# ST_LINK_V2-1.net
KiCad netlist of a schematic drawn in Altium Designer
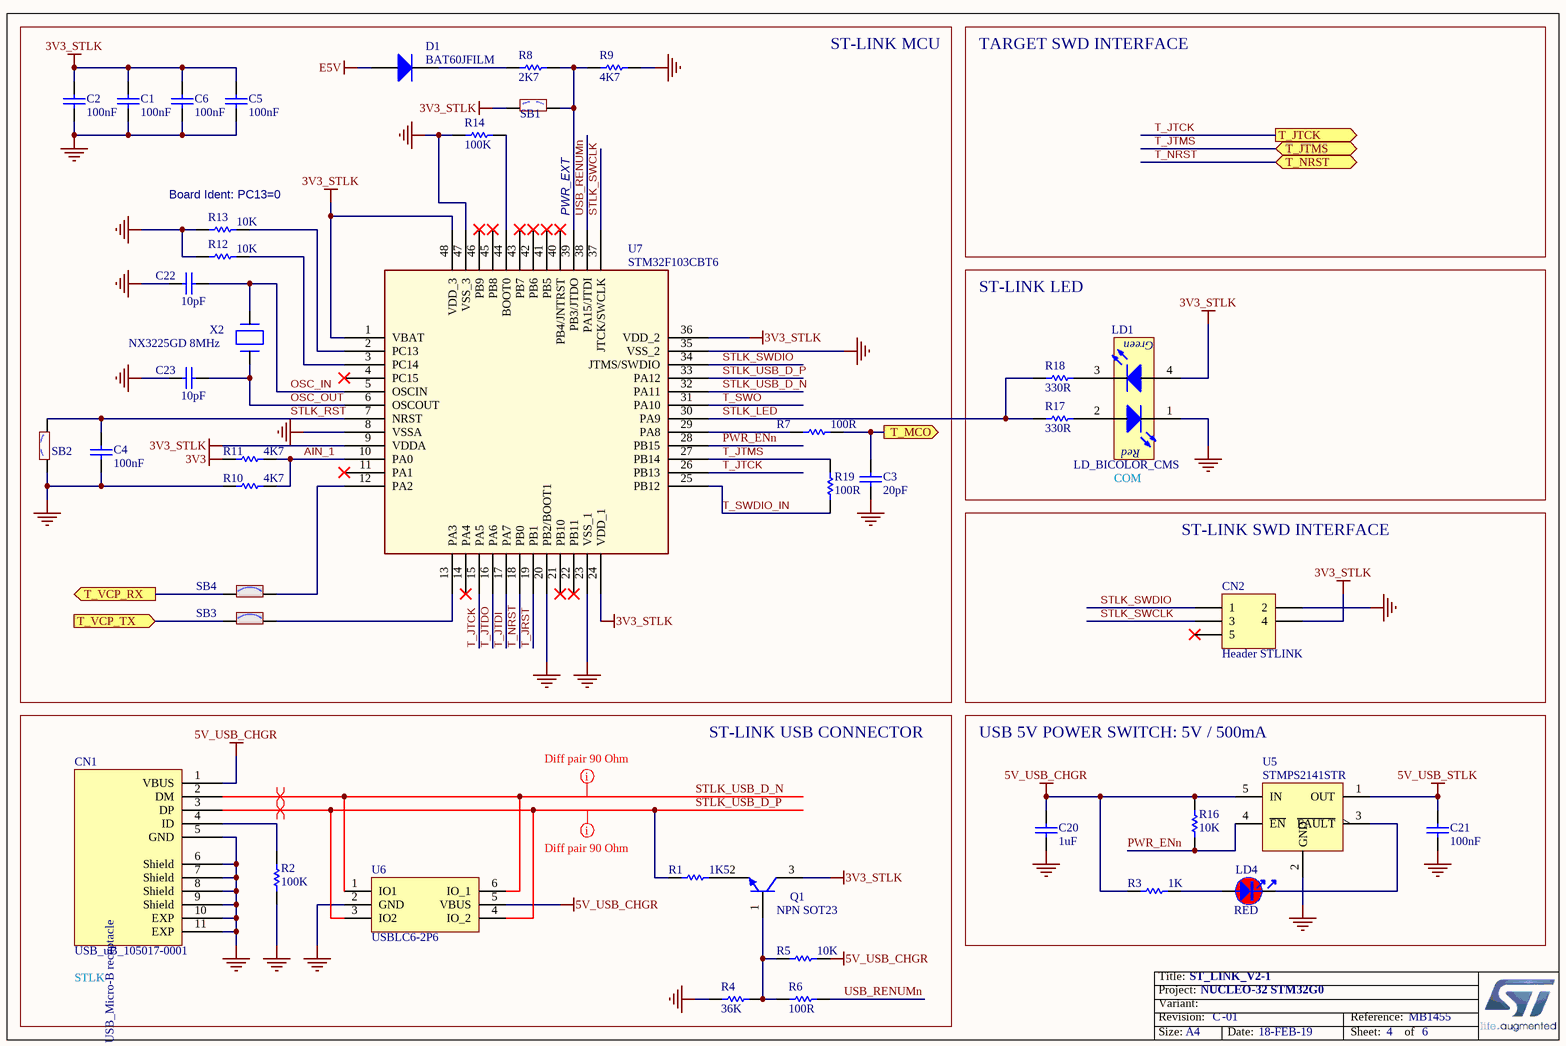
[diagram p0: ST_LINK_V2-1.SCHDOC]

(export (version "E")
  (design (tool "Eeschema 10.0.6"))
  (components
    (comp (ref "C1")
      (value "100nF")
      (footprint "C0402")
      (description "Capacitor, MLCC, 100nF, 16V, X7R, 10%, 0402, T=0,5mm")
      (fields
        (field (name "INTERNAL_PART_NUMBER") "MCD-00102")
        (field (name "MANUFACTURER_PART_NUMBER") "CC0402KRX7R7BB104")
        (field (name "PROVIDED_BY") "SUBCO")
      )
      (libsource (lib "MCD_PARTS_database") (part "Capacitor"))
    )
    (comp (ref "C2")
      (value "100nF")
      (footprint "C0402")
      (description "Capacitor, MLCC, 100nF, 16V, X7R, 10%, 0402, T=0,5mm")
      (fields
        (field (name "INTERNAL_PART_NUMBER") "MCD-00102")
        (field (name "MANUFACTURER_PART_NUMBER") "CC0402KRX7R7BB104")
        (field (name "PROVIDED_BY") "SUBCO")
      )
      (libsource (lib "MCD_PARTS_database") (part "Capacitor"))
    )
    (comp (ref "C3")
      (value "20pF")
      (footprint "C0402")
      (description "Capacitor, MLCC, 20pF, 50V, NPO, 5%, 0402, T=0,5mm")
      (fields
        (field (name "INTERNAL_PART_NUMBER") "MCD-00016")
        (field (name "MANUFACTURER_PART_NUMBER") "CC0402JRNPO9BN200")
        (field (name "PROVIDED_BY") "SUBCO")
      )
      (libsource (lib "MCD_PARTS_database") (part "Capacitor"))
    )
    (comp (ref "C4")
      (value "100nF")
      (footprint "C0402")
      (description "Capacitor, MLCC, 100nF, 16V, X7R, 10%, 0402, T=0,5mm")
      (fields
        (field (name "INTERNAL_PART_NUMBER") "MCD-00102")
        (field (name "MANUFACTURER_PART_NUMBER") "CC0402KRX7R7BB104")
        (field (name "PROVIDED_BY") "SUBCO")
      )
      (libsource (lib "MCD_PARTS_database") (part "Capacitor"))
    )
    (comp (ref "C5")
      (value "100nF")
      (footprint "C0402")
      (description "Capacitor, MLCC, 100nF, 16V, X7R, 10%, 0402, T=0,5mm")
      (fields
        (field (name "INTERNAL_PART_NUMBER") "MCD-00102")
        (field (name "MANUFACTURER_PART_NUMBER") "CC0402KRX7R7BB104")
        (field (name "PROVIDED_BY") "SUBCO")
      )
      (libsource (lib "MCD_PARTS_database") (part "Capacitor"))
    )
    (comp (ref "C6")
      (value "100nF")
      (footprint "C0402")
      (description "Capacitor, MLCC, 100nF, 16V, X7R, 10%, 0402, T=0,5mm")
      (fields
        (field (name "INTERNAL_PART_NUMBER") "MCD-00102")
        (field (name "MANUFACTURER_PART_NUMBER") "CC0402KRX7R7BB104")
        (field (name "PROVIDED_BY") "SUBCO")
      )
      (libsource (lib "MCD_PARTS_database") (part "Capacitor"))
    )
    (comp (ref "C20")
      (value "1uF")
      (footprint "C0402")
      (description "Capacitor, MLCC, 1uF, 6V3, X5R, 10%, 0402, T=0,5mm")
      (fields
        (field (name "INTERNAL_PART_NUMBER") "MCD-00095")
        (field (name "MANUFACTURER_PART_NUMBER") "GRM155R61E105KA12")
        (field (name "PROVIDED_BY") "SUBCO")
      )
      (libsource (lib "MCD_PARTS_database") (part "Capacitor"))
    )
    (comp (ref "C21")
      (value "100nF")
      (footprint "C0402")
      (description "Capacitor, MLCC, 100nF, 16V, X7R, 10%, 0402, T=0,5mm")
      (fields
        (field (name "INTERNAL_PART_NUMBER") "MCD-00102")
        (field (name "MANUFACTURER_PART_NUMBER") "CC0402KRX7R7BB104")
        (field (name "PROVIDED_BY") "SUBCO")
      )
      (libsource (lib "MCD_PARTS_database") (part "Capacitor"))
    )
    (comp (ref "C22")
      (value "10pF")
      (footprint "C0402")
      (description "Capacitor, MLCC, 10pF, 50V, NPO, 5%, 0402, T=0,5mm")
      (fields
        (field (name "INTERNAL_PART_NUMBER") "MCD-00015")
        (field (name "MANUFACTURER_PART_NUMBER") "CC0402JRNPO9BN100")
        (field (name "PROVIDED_BY") "SUBCO")
      )
      (libsource (lib "MCD_PARTS_database") (part "Capacitor"))
    )
    (comp (ref "C23")
      (value "10pF")
      (footprint "C0402")
      (description "Capacitor, MLCC, 10pF, 50V, NPO, 5%, 0402, T=0,5mm")
      (fields
        (field (name "INTERNAL_PART_NUMBER") "MCD-00015")
        (field (name "MANUFACTURER_PART_NUMBER") "CC0402JRNPO9BN100")
        (field (name "PROVIDED_BY") "SUBCO")
      )
      (libsource (lib "MCD_PARTS_database") (part "Capacitor"))
    )
    (comp (ref "CN1")
      (value "USB_uB_105017-0001")
      (footprint "CON_USBMICROB_MOLEX_105017-0001_H2P90")
      (description "USB-MICRO-B, 0.65mm, RA, SMT, Bottom Mount,")
      (fields
        (field (name "INTERNAL_PART_NUMBER") "MCD-00028")
        (field (name "MANUFACTURER_PART_NUMBER") "1050170001")
        (field (name "PROVIDED_BY") "SUBCO")
      )
      (libsource (lib "MCD_PARTS_database") (part "USB_uB_105017.0001"))
    )
    (comp (ref "CN2")
      (value "Header STLINK")
      (footprint "HDR_1x5_2R54_V_M")
      (description "Header 5 pads for ST-LINK prog. Not fitted")
      (fields
        (field (name "INTERNAL_PART_NUMBER") "MCD-01399")
        (field (name "MANUFACTURER_PART_NUMBER") "n/a")
        (field (name "PROVIDED_BY") "SUBCO")
      )
      (libsource (lib "MCD_PARTS_database") (part "Header STLINK"))
    )
    (comp (ref "D1")
      (value "BAT60JFILM")
      (footprint "DIO_SOD323")
      (fields
        (field (name "INTERNAL_PART_NUMBER") "MCD-00034")
        (field (name "MANUFACTURER") "STMICROELECTRONICS")
        (field (name "BMS_PART_NUMBER") "9151097")
        (field (name "PROVIDED_BY") "SUBCO with ST control")
      )
      (libsource (lib "MCD_PARTS_database") (part "BAT60JFILM"))
    )
    (comp (ref "LD1")
      (value "LD_BICOLOR_CMS")
      (footprint "LED_BI-GR_HSMF-A201-A00J1")
      (description "LED Bicolor")
      (fields
        (field (name "INTERNAL_PART_NUMBER") "MCD-00051")
        (field (name "MANUFACTURER_PART_NUMBER") "HSMF-A201-A00J1")
        (field (name "PROVIDED_BY") "SUBCO")
      )
      (libsource (lib "MCD_PARTS_database") (part "LD_BICOLOR_CMS"))
    )
    (comp (ref "LD4")
      (value "RED")
      (footprint "LED_0603_RED_H0P4")
      (description "LED, Red, 0603")
      (fields
        (field (name "INTERNAL_PART_NUMBER") "MCD-00322")
        (field (name "MANUFACTURER_PART_NUMBER") "19-217/R6C-AL1M2VY/3T")
        (field (name "PROVIDED_BY") "SUBCO")
      )
      (libsource (lib "MCD_PARTS_database") (part "LED_red"))
    )
    (comp (ref "Q1")
      (value "NPN SOT23")
      (footprint "NPN_SOT23")
      (description "NPN Bipolar Transistor")
      (fields
        (field (name "INTERNAL_PART_NUMBER") "MCD-00073")
        (field (name "MANUFACTURER_PART_NUMBER") "BSR14")
        (field (name "PROVIDED_BY") "SUBCO")
      )
      (libsource (lib "MCD_PARTS_database") (part "9013-SOT23"))
    )
    (comp (ref "R1")
      (value "1K5")
      (footprint "R0402")
      (description "Resistor,1K5,0402,1%,1/16W")
      (fields
        (field (name "INTERNAL_PART_NUMBER") "MCD-00068")
        (field (name "MANUFACTURER_PART_NUMBER") "RC0402FR-071K5L")
        (field (name "PROVIDED_BY") "SUBCO")
      )
      (libsource (lib "MCD_PARTS_database") (part "Resistor"))
    )
    (comp (ref "R2")
      (value "100K")
      (footprint "R0402")
      (description "Resistor,100K,0402,1%,1/16W")
      (fields
        (field (name "INTERNAL_PART_NUMBER") "MCD-00059")
        (field (name "MANUFACTURER_PART_NUMBER") "RC0402FR-07100KL")
        (field (name "PROVIDED_BY") "SUBCO")
      )
      (libsource (lib "MCD_PARTS_database") (part "Resistor"))
    )
    (comp (ref "R3")
      (value "1K")
      (footprint "R0402")
      (description "Resistor,1K,0402,1%,1/16W")
      (fields
        (field (name "INTERNAL_PART_NUMBER") "MCD-00061")
        (field (name "MANUFACTURER_PART_NUMBER") "RC0402FR-071KL")
        (field (name "PROVIDED_BY") "SUBCO")
      )
      (libsource (lib "MCD_PARTS_database") (part "Resistor"))
    )
    (comp (ref "R4")
      (value "36K")
      (footprint "R0402")
      (description "Resistor,36K,0402,1%,1/16W")
      (fields
        (field (name "INTERNAL_PART_NUMBER") "MCD-00069")
        (field (name "MANUFACTURER_PART_NUMBER") "RC0402FR-0736KL")
        (field (name "PROVIDED_BY") "SUBCO")
      )
      (libsource (lib "MCD_PARTS_database") (part "Resistor"))
    )
    (comp (ref "R5")
      (value "10K")
      (footprint "R0402")
      (description "Resistor,10K,0402,1%,1/16W")
      (fields
        (field (name "INTERNAL_PART_NUMBER") "MCD-00053")
        (field (name "MANUFACTURER_PART_NUMBER") "RC0402FR-0710KL")
        (field (name "PROVIDED_BY") "SUBCO")
      )
      (libsource (lib "MCD_PARTS_database") (part "Resistor"))
    )
    (comp (ref "R6")
      (value "100R")
      (footprint "R0402")
      (description "Resistor,100R,0402,1%,1/16W")
      (fields
        (field (name "INTERNAL_PART_NUMBER") "MCD-00067")
        (field (name "MANUFACTURER_PART_NUMBER") "RC0402FR-07100RL")
        (field (name "PROVIDED_BY") "SUBCO")
      )
      (libsource (lib "MCD_PARTS_database") (part "Resistor"))
    )
    (comp (ref "R7")
      (value "100R")
      (footprint "R0402")
      (description "Resistor,100R,0402,1%,1/16W")
      (fields
        (field (name "INTERNAL_PART_NUMBER") "MCD-00067")
        (field (name "MANUFACTURER_PART_NUMBER") "RC0402FR-07100RL")
        (field (name "PROVIDED_BY") "SUBCO")
      )
      (libsource (lib "MCD_PARTS_database") (part "Resistor"))
    )
    (comp (ref "R8")
      (value "2K7")
      (footprint "R0402")
      (description "Resistor,2K7,0402,1%,1/16W")
      (fields
        (field (name "INTERNAL_PART_NUMBER") "MCD-00055")
        (field (name "MANUFACTURER_PART_NUMBER") "RC0402FR-072K7L")
        (field (name "PROVIDED_BY") "SUBCO")
      )
      (libsource (lib "MCD_PARTS_database") (part "Resistor"))
    )
    (comp (ref "R9")
      (value "4K7")
      (footprint "R0402")
      (description "Resistor,4K7,0402,1%,1/16W")
      (fields
        (field (name "INTERNAL_PART_NUMBER") "MCD-00065")
        (field (name "MANUFACTURER_PART_NUMBER") "RC0402FR-074K7L")
        (field (name "PROVIDED_BY") "SUBCO")
      )
      (libsource (lib "MCD_PARTS_database") (part "Resistor"))
    )
    (comp (ref "R10")
      (value "4K7")
      (footprint "R0402")
      (description "Resistor,4K7,0402,1%,1/16W")
      (fields
        (field (name "INTERNAL_PART_NUMBER") "MCD-00065")
        (field (name "MANUFACTURER_PART_NUMBER") "RC0402FR-074K7L")
        (field (name "PROVIDED_BY") "SUBCO")
      )
      (libsource (lib "MCD_PARTS_database") (part "Resistor"))
    )
    (comp (ref "R11")
      (value "4K7")
      (footprint "R0402")
      (description "Resistor,4K7,0402,1%,1/16W")
      (fields
        (field (name "INTERNAL_PART_NUMBER") "MCD-00065")
        (field (name "MANUFACTURER_PART_NUMBER") "RC0402FR-074K7L")
        (field (name "PROVIDED_BY") "SUBCO")
      )
      (libsource (lib "MCD_PARTS_database") (part "Resistor"))
    )
    (comp (ref "R12")
      (value "10K")
      (footprint "R0402")
      (description "Resistor,10K,0402,1%,1/16W")
      (fields
        (field (name "INTERNAL_PART_NUMBER") "MCD-00053")
        (field (name "MANUFACTURER_PART_NUMBER") "RC0402FR-0710KL")
        (field (name "PROVIDED_BY") "SUBCO")
      )
      (libsource (lib "MCD_PARTS_database") (part "Resistor"))
    )
    (comp (ref "R13")
      (value "10K")
      (footprint "R0402")
      (description "Resistor,10K,0402,1%,1/16W")
      (fields
        (field (name "INTERNAL_PART_NUMBER") "MCD-00053")
        (field (name "MANUFACTURER_PART_NUMBER") "RC0402FR-0710KL")
        (field (name "PROVIDED_BY") "SUBCO")
      )
      (libsource (lib "MCD_PARTS_database") (part "Resistor"))
    )
    (comp (ref "R14")
      (value "100K")
      (footprint "R0402")
      (description "Resistor,100K,0402,1%,1/16W")
      (fields
        (field (name "INTERNAL_PART_NUMBER") "MCD-00059")
        (field (name "MANUFACTURER_PART_NUMBER") "RC0402FR-07100KL")
        (field (name "PROVIDED_BY") "SUBCO")
      )
      (libsource (lib "MCD_PARTS_database") (part "Resistor"))
    )
    (comp (ref "R16")
      (value "10K")
      (footprint "R0402")
      (description "Resistor,10K,0402,1%,1/16W")
      (fields
        (field (name "INTERNAL_PART_NUMBER") "MCD-00053")
        (field (name "MANUFACTURER_PART_NUMBER") "RC0402FR-0710KL")
        (field (name "PROVIDED_BY") "SUBCO")
      )
      (libsource (lib "MCD_PARTS_database") (part "Resistor"))
    )
    (comp (ref "R17")
      (value "330R")
      (footprint "R0402")
      (description "Resistor,330R,0402,1%,1/16W")
      (fields
        (field (name "INTERNAL_PART_NUMBER") "MCD-00062")
        (field (name "MANUFACTURER_PART_NUMBER") "RC0402FR-07330RL")
        (field (name "PROVIDED_BY") "SUBCO")
      )
      (libsource (lib "MCD_PARTS_database") (part "Resistor"))
    )
    (comp (ref "R18")
      (value "330R")
      (footprint "R0402")
      (description "Resistor,330R,0402,1%,1/16W")
      (fields
        (field (name "INTERNAL_PART_NUMBER") "MCD-00062")
        (field (name "MANUFACTURER_PART_NUMBER") "RC0402FR-07330RL")
        (field (name "PROVIDED_BY") "SUBCO")
      )
      (libsource (lib "MCD_PARTS_database") (part "Resistor"))
    )
    (comp (ref "R19")
      (value "100R")
      (footprint "R0402")
      (description "Resistor,100R,0402,1%,1/16W")
      (fields
        (field (name "INTERNAL_PART_NUMBER") "MCD-00067")
        (field (name "MANUFACTURER_PART_NUMBER") "RC0402FR-07100RL")
        (field (name "PROVIDED_BY") "SUBCO")
      )
      (libsource (lib "MCD_PARTS_database") (part "Resistor"))
    )
    (comp (ref "SB1")
      (value "SB_OFF")
      (footprint "SOLDER-BRIDGE_R0603-0R")
      (description "Solder Bridge OFF")
      (fields
        (field (name "INTERNAL_PART_NUMBER") "MCD-00072")
        (field (name "MANUFACTURER_PART_NUMBER") "RC0603JR-070RL")
        (field (name "PROVIDED_BY") "SUBCO")
      )
      (libsource (lib "") (part "SB_OFF_1"))
    )
    (comp (ref "SB2")
      (value "SB_OFF")
      (footprint "SOLDER-BRIDGE_R0603-0R")
      (description "Solder Bridge OFF")
      (fields
        (field (name "INTERNAL_PART_NUMBER") "MCD-00072")
        (field (name "MANUFACTURER_PART_NUMBER") "RC0603JR-070RL")
        (field (name "PROVIDED_BY") "SUBCO")
      )
      (libsource (lib "MCD_PARTS_database") (part "SB_OFF"))
    )
    (comp (ref "SB3")
      (value "SB_ON")
      (footprint "SOLDER-BRIDGE_R0603-0R")
      (description "Solder Bridge ON")
      (fields
        (field (name "INTERNAL_PART_NUMBER") "MCD-00071")
        (field (name "MANUFACTURER_PART_NUMBER") "RC0603JR-070RL")
        (field (name "PROVIDED_BY") "SUBCO")
      )
      (libsource (lib "MCD_PARTS_database") (part "SB_ON"))
    )
    (comp (ref "SB4")
      (value "SB_ON")
      (footprint "SOLDER-BRIDGE_R0603-0R")
      (description "Solder Bridge ON")
      (fields
        (field (name "INTERNAL_PART_NUMBER") "MCD-00071")
        (field (name "MANUFACTURER_PART_NUMBER") "RC0603JR-070RL")
        (field (name "PROVIDED_BY") "SUBCO")
      )
      (libsource (lib "MCD_PARTS_database") (part "SB_ON"))
    )
    (comp (ref "U5")
      (value "STMPS2141STR")
      (footprint "MOS_SOT23-5L")
      (description "Enhanced single channel power switches with active low enable pin")
      (fields
        (field (name "INTERNAL_PART_NUMBER") "MCD-00083")
        (field (name "MANUFACTURER") "STMICROELECTRONICS")
        (field (name "PROVIDED_BY") "SUBCO with ST control")
      )
      (libsource (lib "MCD_PARTS_database") (part "STMPS2141STR"))
    )
    (comp (ref "U6")
      (value "USBLC6-2P6")
      (footprint "ESD_SOT666")
      (description "USB OTG FS ESD protection")
      (fields
        (field (name "INTERNAL_PART_NUMBER") "MCD-00169")
        (field (name "MANUFACTURER") "STMICROELECTRONICS")
        (field (name "PROVIDED_BY") "SUBCO with ST control")
      )
      (libsource (lib "MCD_PARTS_database") (part "USBLC6-2P6"))
    )
    (comp (ref "U7")
      (value "STM32F103CBT6")
      (footprint "ICC_LQFP48_7X7_P050")
      (description "Medium-density performance line ARM-based 32-bit MCU with 128KB Flash")
      (fields
        (field (name "INTERNAL_PART_NUMBER") "MCD-00085")
        (field (name "MANUFACTURER") "STMICROELECTRONICS")
        (field (name "PROVIDED_BY") "SUBCO with ST control")
      )
      (libsource (lib "MCD_PARTS_database") (part "STM32F103CBT6"))
    )
    (comp (ref "X2")
      (value "NX3225GD 8MHz")
      (footprint "CRY_NX3225GD_2P")
      (description "Crystal 8MHz, 8pF, +-20ppm, 500ohms max,  SMD")
      (fields
        (field (name "INTERNAL_PART_NUMBER") "MCD-00092")
        (field (name "MANUFACTURER_PART_NUMBER") "NX3225GD 8MHz EXS00A-CG04874")
        (field (name "PROVIDED_BY") "SUBCO")
      )
      (libsource (lib "MCD_PARTS_database") (part "XTAL_2_PINS"))
    )
  )
  (nets
    (net (code "1") (name "/AIN_1") (class "Default")
      (node (ref "R10") (pin "2") (pinfunction "2_2") (pintype "passive"))
      (node (ref "R11") (pin "2") (pinfunction "2_2") (pintype "passive"))
      (node (ref "U7") (pin "10") (pinfunction "PA0_10") (pintype "passive"))
    )
    (net (code "2") (name "/OSC_IN") (class "Default")
      (node (ref "C22") (pin "2") (pinfunction "2_2") (pintype "passive"))
      (node (ref "U7") (pin "5") (pinfunction "OSCIN_5") (pintype "passive"))
      (node (ref "X2") (pin "1") (pinfunction "X1_1") (pintype "passive"))
    )
    (net (code "3") (name "/OSC_OUT") (class "Default")
      (node (ref "C23") (pin "2") (pinfunction "2_2") (pintype "passive"))
      (node (ref "U7") (pin "6") (pinfunction "OSCOUT_6") (pintype "passive"))
      (node (ref "X2") (pin "2") (pinfunction "X2_2") (pintype "passive"))
    )
    (net (code "4") (name "/PWR_ENn") (class "Default")
      (node (ref "R16") (pin "1") (pinfunction "1_1") (pintype "passive"))
      (node (ref "U5") (pin "4") (pinfunction "~{EN}_4") (pintype "passive"))
      (node (ref "U7") (pin "28") (pinfunction "PB15_28") (pintype "passive"))
    )
    (net (code "5") (name "/STLK_LED") (class "Default")
      (node (ref "R17") (pin "1") (pinfunction "1_1") (pintype "passive"))
      (node (ref "R18") (pin "1") (pinfunction "1_1") (pintype "passive"))
      (node (ref "U7") (pin "30") (pinfunction "PA9_30") (pintype "passive"))
    )
    (net (code "6") (name "/STLK_RST") (class "Default")
      (node (ref "C4") (pin "2") (pinfunction "2_2") (pintype "passive"))
      (node (ref "SB2") (pin "2") (pinfunction "2_2") (pintype "passive"))
      (node (ref "U7") (pin "7") (pinfunction "NRST_7") (pintype "passive"))
    )
    (net (code "7") (name "/STLK_SWCLK") (class "Default")
      (node (ref "CN2") (pin "3") (pinfunction "3_3") (pintype "passive"))
      (node (ref "U7") (pin "37") (pinfunction "JTCK/SWCLK_37") (pintype "passive"))
    )
    (net (code "8") (name "/STLK_SWDIO") (class "Default")
      (node (ref "CN2") (pin "1") (pinfunction "1_1") (pintype "passive"))
      (node (ref "U7") (pin "34") (pinfunction "JTMS/SWDIO_34") (pintype "passive"))
    )
    (net (code "9") (name "/STLK_USB_D_N") (class "Default")
      (node (ref "CN1") (pin "2") (pinfunction "DM_2") (pintype "passive"))
      (node (ref "U6") (pin "1") (pinfunction "IO1_1") (pintype "passive"))
      (node (ref "U6") (pin "6") (pinfunction "IO_1_6") (pintype "passive"))
      (node (ref "U7") (pin "32") (pinfunction "PA11_32") (pintype "passive"))
    )
    (net (code "10") (name "/STLK_USB_D_P") (class "Default")
      (node (ref "CN1") (pin "3") (pinfunction "DP_3") (pintype "passive"))
      (node (ref "R1") (pin "1") (pinfunction "1_1") (pintype "passive"))
      (node (ref "U6") (pin "3") (pinfunction "IO2_3") (pintype "passive"))
      (node (ref "U6") (pin "4") (pinfunction "IO_2_4") (pintype "passive"))
      (node (ref "U7") (pin "33") (pinfunction "PA12_33") (pintype "passive"))
    )
    (net (code "11") (name "/T_JRST") (class "Default")
      (node (ref "U7") (pin "19") (pinfunction "PB1_19") (pintype "passive"))
    )
    (net (code "12") (name "/T_JTCK") (class "Default")
      (node (ref "U7") (pin "15") (pinfunction "PA5_15") (pintype "passive"))
      (node (ref "U7") (pin "26") (pinfunction "PB13_26") (pintype "passive"))
    )
    (net (code "13") (name "/T_JTDI") (class "Default")
      (node (ref "U7") (pin "17") (pinfunction "PA7_17") (pintype "passive"))
    )
    (net (code "14") (name "/T_JTDO") (class "Default")
      (node (ref "U7") (pin "16") (pinfunction "PA6_16") (pintype "passive"))
    )
    (net (code "15") (name "/T_JTMS") (class "Default")
      (node (ref "R19") (pin "2") (pinfunction "2_2") (pintype "passive"))
      (node (ref "U7") (pin "27") (pinfunction "PB14_27") (pintype "passive"))
    )
    (net (code "16") (name "/T_MCO") (class "Default")
      (node (ref "C3") (pin "2") (pinfunction "2_2") (pintype "passive"))
      (node (ref "R7") (pin "2") (pinfunction "2_2") (pintype "passive"))
    )
    (net (code "17") (name "/T_NRST") (class "Default")
      (node (ref "U7") (pin "18") (pinfunction "PB0_18") (pintype "passive"))
    )
    (net (code "18") (name "/T_SWDIO_IN") (class "Default")
      (node (ref "R19") (pin "1") (pinfunction "1_1") (pintype "passive"))
      (node (ref "U7") (pin "25") (pinfunction "PB12_25") (pintype "passive"))
    )
    (net (code "19") (name "/T_SWO") (class "Default")
      (node (ref "U7") (pin "31") (pinfunction "PA10_31") (pintype "passive"))
    )
    (net (code "20") (name "/T_VCP_RX") (class "Default")
      (node (ref "SB4") (pin "1") (pinfunction "1_1") (pintype "passive"))
    )
    (net (code "21") (name "/T_VCP_TX") (class "Default")
      (node (ref "SB3") (pin "1") (pinfunction "1_1") (pintype "passive"))
    )
    (net (code "22") (name "/USB_RENUMn") (class "Default")
      (node (ref "R6") (pin "2") (pinfunction "2_2") (pintype "passive"))
      (node (ref "U7") (pin "38") (pinfunction "PA15/JTDI_38") (pintype "passive"))
    )
    (net (code "23") (name "3V3") (class "Default")
      (node (ref "R11") (pin "1") (pinfunction "1_1") (pintype "passive"))
    )
    (net (code "24") (name "3V3_STLK") (class "Default")
      (node (ref "C1") (pin "2") (pinfunction "2_2") (pintype "passive"))
      (node (ref "C2") (pin "2") (pinfunction "2_2") (pintype "passive"))
      (node (ref "C5") (pin "2") (pinfunction "2_2") (pintype "passive"))
      (node (ref "C6") (pin "2") (pinfunction "2_2") (pintype "passive"))
      (node (ref "CN2") (pin "4") (pinfunction "4_4") (pintype "passive"))
      (node (ref "LD1") (pin "4") (pinfunction "YellowGreen_anode_4") (pintype "passive"))
      (node (ref "Q1") (pin "3") (pinfunction "C_3") (pintype "passive"))
      (node (ref "SB1") (pin "1") (pinfunction "1_1") (pintype "passive"))
      (node (ref "U7") (pin "1") (pinfunction "VBAT_1") (pintype "passive"))
      (node (ref "U7") (pin "24") (pinfunction "VDD_1_24") (pintype "passive"))
      (node (ref "U7") (pin "36") (pinfunction "VDD_2_36") (pintype "passive"))
      (node (ref "U7") (pin "48") (pinfunction "VDD_3_48") (pintype "passive"))
      (node (ref "U7") (pin "9") (pinfunction "VDDA_9") (pintype "passive"))
    )
    (net (code "25") (name "5V_USB_CHGR") (class "Default")
      (node (ref "C20") (pin "2") (pinfunction "2_2") (pintype "passive"))
      (node (ref "CN1") (pin "1") (pinfunction "VBUS_1") (pintype "passive"))
      (node (ref "R16") (pin "2") (pinfunction "2_2") (pintype "passive"))
      (node (ref "R3") (pin "1") (pinfunction "1_1") (pintype "passive"))
      (node (ref "R5") (pin "2") (pinfunction "2_2") (pintype "passive"))
      (node (ref "U5") (pin "5") (pinfunction "IN_5") (pintype "passive"))
      (node (ref "U6") (pin "5") (pinfunction "VBUS_5") (pintype "passive"))
    )
    (net (code "26") (name "5V_USB_STLK") (class "Default")
      (node (ref "C21") (pin "2") (pinfunction "2_2") (pintype "passive"))
      (node (ref "U5") (pin "1") (pinfunction "OUT_1") (pintype "passive"))
    )
    (net (code "27") (name "E5V") (class "Default")
      (node (ref "D1") (pin "1") (pinfunction "A_1") (pintype "passive"))
    )
    (net (code "28") (name "GND") (class "Default")
      (node (ref "C1") (pin "1") (pinfunction "1_1") (pintype "passive"))
      (node (ref "C2") (pin "1") (pinfunction "1_1") (pintype "passive"))
      (node (ref "C20") (pin "1") (pinfunction "1_1") (pintype "passive"))
      (node (ref "C21") (pin "1") (pinfunction "1_1") (pintype "passive"))
      (node (ref "C22") (pin "1") (pinfunction "1_1") (pintype "passive"))
      (node (ref "C23") (pin "1") (pinfunction "1_1") (pintype "passive"))
      (node (ref "C3") (pin "1") (pinfunction "1_1") (pintype "passive"))
      (node (ref "C4") (pin "1") (pinfunction "1_1") (pintype "passive"))
      (node (ref "C5") (pin "1") (pinfunction "1_1") (pintype "passive"))
      (node (ref "C6") (pin "1") (pinfunction "1_1") (pintype "passive"))
      (node (ref "CN1") (pin "10") (pinfunction "EXP_10") (pintype "passive"))
      (node (ref "CN1") (pin "11") (pinfunction "EXP_11") (pintype "passive"))
      (node (ref "CN1") (pin "5") (pinfunction "GND_5") (pintype "passive"))
      (node (ref "CN1") (pin "6") (pinfunction "Shield_6") (pintype "passive"))
      (node (ref "CN1") (pin "7") (pinfunction "Shield_7") (pintype "passive"))
      (node (ref "CN1") (pin "8") (pinfunction "Shield_8") (pintype "passive"))
      (node (ref "CN1") (pin "9") (pinfunction "Shield_9") (pintype "passive"))
      (node (ref "CN2") (pin "2") (pinfunction "2_2") (pintype "passive"))
      (node (ref "LD1") (pin "1") (pinfunction "RED_cathode_1") (pintype "passive"))
      (node (ref "R10") (pin "1") (pinfunction "1_1") (pintype "passive"))
      (node (ref "R12") (pin "1") (pinfunction "1_1") (pintype "passive"))
      (node (ref "R13") (pin "1") (pinfunction "1_1") (pintype "passive"))
      (node (ref "R14") (pin "1") (pinfunction "1_1") (pintype "passive"))
      (node (ref "R2") (pin "1") (pinfunction "1_1") (pintype "passive"))
      (node (ref "R4") (pin "1") (pinfunction "1_1") (pintype "passive"))
      (node (ref "R9") (pin "2") (pinfunction "2_2") (pintype "passive"))
      (node (ref "SB2") (pin "1") (pinfunction "1_1") (pintype "passive"))
      (node (ref "U5") (pin "2") (pinfunction "GND_2") (pintype "passive"))
      (node (ref "U6") (pin "2") (pinfunction "GND_2") (pintype "passive"))
      (node (ref "U7") (pin "20") (pinfunction "PB2/BOOT1_20") (pintype "passive"))
      (node (ref "U7") (pin "23") (pinfunction "VSS_1_23") (pintype "passive"))
      (node (ref "U7") (pin "35") (pinfunction "VSS_2_35") (pintype "passive"))
      (node (ref "U7") (pin "47") (pinfunction "VSS_3_47") (pintype "passive"))
      (node (ref "U7") (pin "8") (pinfunction "VSSA_8") (pintype "passive"))
    )
    (net (code "29") (name "Net-(CN1-ID)") (class "Default")
      (node (ref "CN1") (pin "4") (pinfunction "ID_4") (pintype "passive"))
      (node (ref "R2") (pin "2") (pinfunction "2_2") (pintype "passive"))
    )
    (net (code "30") (name "Net-(D1-K)") (class "Default")
      (node (ref "D1") (pin "2") (pinfunction "K_2") (pintype "passive"))
      (node (ref "R8") (pin "1") (pinfunction "1_1") (pintype "passive"))
    )
    (net (code "31") (name "Net-(LD1-Red_anode)") (class "Default")
      (node (ref "LD1") (pin "2") (pinfunction "Red_anode_2") (pintype "passive"))
      (node (ref "R17") (pin "2") (pinfunction "2_2") (pintype "passive"))
    )
    (net (code "32") (name "Net-(LD1-YellowGreen_cathode)") (class "Default")
      (node (ref "LD1") (pin "3") (pinfunction "YellowGreen_cathode_3") (pintype "passive"))
      (node (ref "R18") (pin "2") (pinfunction "2_2") (pintype "passive"))
    )
    (net (code "33") (name "Net-(LD4-Pad1)") (class "Default")
      (node (ref "LD4") (pin "1") (pintype "passive"))
      (node (ref "R3") (pin "2") (pinfunction "2_2") (pintype "passive"))
    )
    (net (code "34") (name "Net-(Q1-B)") (class "Default")
      (node (ref "Q1") (pin "1") (pinfunction "B_1") (pintype "passive"))
      (node (ref "R4") (pin "2") (pinfunction "2_2") (pintype "passive"))
      (node (ref "R5") (pin "1") (pinfunction "1_1") (pintype "passive"))
      (node (ref "R6") (pin "1") (pinfunction "1_1") (pintype "passive"))
    )
    (net (code "35") (name "Net-(Q1-E)") (class "Default")
      (node (ref "Q1") (pin "2") (pinfunction "E_2") (pintype "passive"))
      (node (ref "R1") (pin "2") (pinfunction "2_2") (pintype "passive"))
    )
    (net (code "36") (name "Net-(U5-~{FAULT})") (class "Default")
      (node (ref "LD4") (pin "2") (pintype "passive"))
      (node (ref "U5") (pin "3") (pinfunction "~{FAULT}_3") (pintype "passive"))
    )
    (net (code "37") (name "Net-(U7-BOOT0)") (class "Default")
      (node (ref "R14") (pin "2") (pinfunction "2_2") (pintype "passive"))
      (node (ref "U7") (pin "44") (pinfunction "BOOT0_44") (pintype "passive"))
    )
    (net (code "38") (name "Net-(U7-PA2)") (class "Default")
      (node (ref "SB4") (pin "2") (pinfunction "2_2") (pintype "passive"))
      (node (ref "U7") (pin "12") (pinfunction "PA2_12") (pintype "passive"))
    )
    (net (code "39") (name "Net-(U7-PA3)") (class "Default")
      (node (ref "SB3") (pin "2") (pinfunction "2_2") (pintype "passive"))
      (node (ref "U7") (pin "13") (pinfunction "PA3_13") (pintype "passive"))
    )
    (net (code "40") (name "Net-(U7-PA8)") (class "Default")
      (node (ref "R7") (pin "1") (pinfunction "1_1") (pintype "passive"))
      (node (ref "U7") (pin "29") (pinfunction "PA8_29") (pintype "passive"))
    )
    (net (code "41") (name "Net-(U7-PB3{slash}JTDO)") (class "Default")
      (node (ref "R8") (pin "2") (pinfunction "2_2") (pintype "passive"))
      (node (ref "R9") (pin "1") (pinfunction "1_1") (pintype "passive"))
      (node (ref "SB1") (pin "2") (pinfunction "2_2") (pintype "passive"))
      (node (ref "U7") (pin "39") (pinfunction "PB3/JTDO_39") (pintype "passive"))
    )
    (net (code "42") (name "Net-(U7-PC13)") (class "Default")
      (node (ref "R13") (pin "2") (pinfunction "2_2") (pintype "passive"))
      (node (ref "U7") (pin "2") (pinfunction "PC13_2") (pintype "passive"))
    )
    (net (code "43") (name "Net-(U7-PC14)") (class "Default")
      (node (ref "R12") (pin "2") (pinfunction "2_2") (pintype "passive"))
      (node (ref "U7") (pin "3") (pinfunction "PC14_3") (pintype "passive"))
    )
    (net (code "44") (name "unconnected-(CN2-Pad5)") (class "Default")
      (node (ref "CN2") (pin "5") (pinfunction "5_5") (pintype "passive+no_connect"))
    )
    (net (code "45") (name "unconnected-(U7-PA1-Pad11)") (class "Default")
      (node (ref "U7") (pin "11") (pinfunction "PA1_11") (pintype "passive+no_connect"))
    )
    (net (code "46") (name "unconnected-(U7-PA4-Pad14)") (class "Default")
      (node (ref "U7") (pin "14") (pinfunction "PA4_14") (pintype "passive+no_connect"))
    )
    (net (code "47") (name "unconnected-(U7-PB4{slash}JNTRST-Pad40)") (class "Default")
      (node (ref "U7") (pin "40") (pinfunction "PB4/JNTRST_40") (pintype "passive+no_connect"))
    )
    (net (code "48") (name "unconnected-(U7-PB5-Pad41)") (class "Default")
      (node (ref "U7") (pin "41") (pinfunction "PB5_41") (pintype "passive+no_connect"))
    )
    (net (code "49") (name "unconnected-(U7-PB6-Pad42)") (class "Default")
      (node (ref "U7") (pin "42") (pinfunction "PB6_42") (pintype "passive+no_connect"))
    )
    (net (code "50") (name "unconnected-(U7-PB7-Pad43)") (class "Default")
      (node (ref "U7") (pin "43") (pinfunction "PB7_43") (pintype "passive+no_connect"))
    )
    (net (code "51") (name "unconnected-(U7-PB8-Pad45)") (class "Default")
      (node (ref "U7") (pin "45") (pinfunction "PB8_45") (pintype "passive+no_connect"))
    )
    (net (code "52") (name "unconnected-(U7-PB9-Pad46)") (class "Default")
      (node (ref "U7") (pin "46") (pinfunction "PB9_46") (pintype "passive+no_connect"))
    )
    (net (code "53") (name "unconnected-(U7-PB10-Pad21)") (class "Default")
      (node (ref "U7") (pin "21") (pinfunction "PB10_21") (pintype "passive+no_connect"))
    )
    (net (code "54") (name "unconnected-(U7-PB11-Pad22)") (class "Default")
      (node (ref "U7") (pin "22") (pinfunction "PB11_22") (pintype "passive+no_connect"))
    )
    (net (code "55") (name "unconnected-(U7-PC15-Pad4)") (class "Default")
      (node (ref "U7") (pin "4") (pinfunction "PC15_4") (pintype "passive+no_connect"))
    )
  )
)
